# moistureMeasure.net
KiCad netlist of a schematic drawn in EAGLE
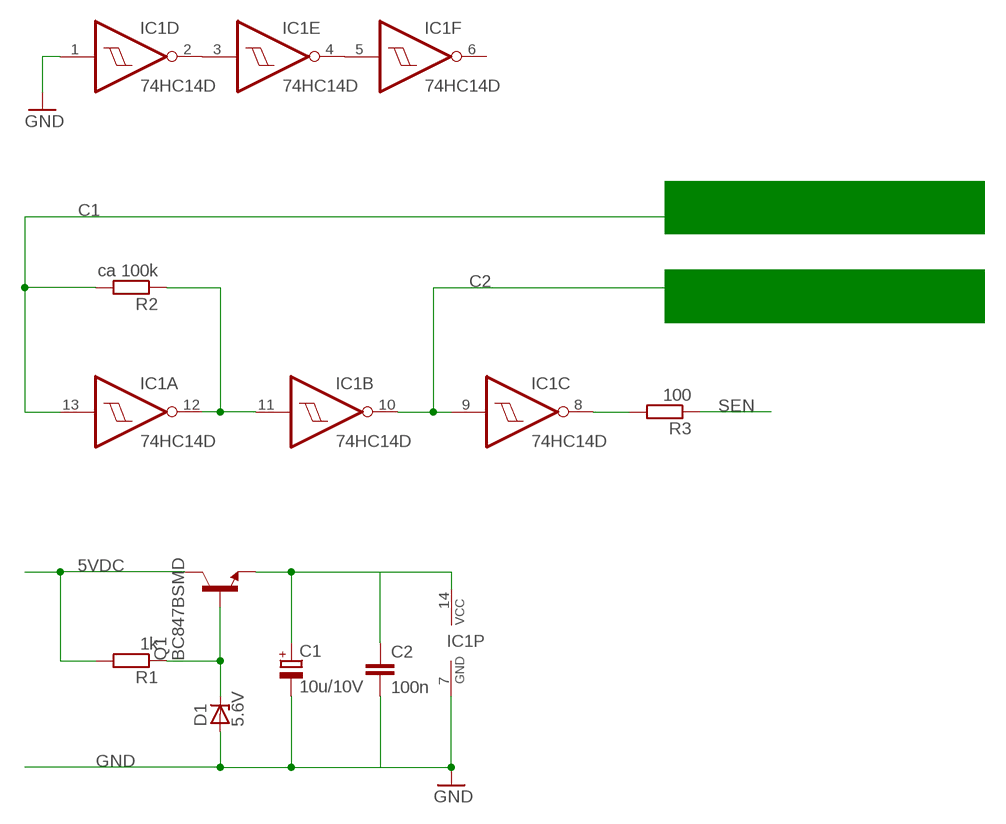
[diagram p0: schematic, sheet 1]

(export (version "E")
  (design (tool "Eeschema 10.0.6"))
  (components
    (comp (ref "C1")
      (value "10u/10V")
      (footprint "eagle-import:A_3216-18W")
      (libsource (lib "eagle-import") (part "CPOL-EUA/3216-18W"))
    )
    (comp (ref "C2")
      (value "100n")
      (footprint "eagle-import:C0805")
      (libsource (lib "eagle-import") (part "C-EUC0805"))
    )
    (comp (ref "D1")
      (value "5.6V")
      (footprint "eagle-import:SOD80C")
      (libsource (lib "eagle-import") (part "ZENER-DIODESOD80C"))
    )
    (comp (ref "IC1")
      (value "74HC14D")
      (footprint "eagle-import:SO14")
      (libsource (lib "eagle-import") (part "7414DHC"))
    )
    (comp (ref "Q1")
      (value "BC847BSMD")
      (footprint "eagle-import:SOT23")
      (libsource (lib "eagle-import") (part "BC847SMDB"))
    )
    (comp (ref "R1")
      (value "1k")
      (footprint "eagle-import:R0805")
      (libsource (lib "eagle-import") (part "R-EU_R0805"))
    )
    (comp (ref "R2")
      (value "ca 100k")
      (footprint "eagle-import:R0805")
      (libsource (lib "eagle-import") (part "R-EU_R0805"))
    )
    (comp (ref "R3")
      (value "100")
      (footprint "eagle-import:R0805")
      (libsource (lib "eagle-import") (part "R-EU_R0805"))
    )
  )
  (nets
    (net (code "1") (name "/5VDC") (class "Default")
      (node (ref "Q1") (pin "3") (pinfunction "C_3") (pintype "passive"))
      (node (ref "R1") (pin "2") (pinfunction "2_2") (pintype "passive"))
    )
    (net (code "2") (name "/C1") (class "Default")
      (node (ref "IC1") (pin "13") (pinfunction "I_13") (pintype "input"))
      (node (ref "R2") (pin "2") (pinfunction "2_2") (pintype "passive"))
    )
    (net (code "3") (name "/C2") (class "Default")
      (node (ref "IC1") (pin "10") (pinfunction "O_10") (pintype "output"))
      (node (ref "IC1") (pin "9") (pinfunction "I_9") (pintype "input"))
    )
    (net (code "4") (name "/SEN") (class "Default")
      (node (ref "R3") (pin "1") (pinfunction "1_1") (pintype "passive"))
    )
    (net (code "5") (name "GND") (class "Default")
      (node (ref "C1") (pin "-") (pinfunction "-_-") (pintype "passive"))
      (node (ref "C2") (pin "2") (pinfunction "2_2") (pintype "passive"))
      (node (ref "D1") (pin "A") (pinfunction "A_A") (pintype "passive"))
      (node (ref "IC1") (pin "1") (pinfunction "I_1") (pintype "input"))
      (node (ref "IC1") (pin "7") (pinfunction "GND_7") (pintype "power_in"))
    )
    (net (code "6") (name "Net-(IC1A-O)") (class "Default")
      (node (ref "IC1") (pin "11") (pinfunction "I_11") (pintype "input"))
      (node (ref "IC1") (pin "12") (pinfunction "O_12") (pintype "output"))
      (node (ref "R2") (pin "1") (pinfunction "1_1") (pintype "passive"))
    )
    (net (code "7") (name "Net-(IC1C-O)") (class "Default")
      (node (ref "IC1") (pin "8") (pinfunction "O_8") (pintype "output"))
      (node (ref "R3") (pin "2") (pinfunction "2_2") (pintype "passive"))
    )
    (net (code "8") (name "Net-(IC1D-O)") (class "Default")
      (node (ref "IC1") (pin "2") (pinfunction "O_2") (pintype "output"))
      (node (ref "IC1") (pin "3") (pinfunction "I_3") (pintype "input"))
    )
    (net (code "9") (name "Net-(IC1E-O)") (class "Default")
      (node (ref "IC1") (pin "4") (pinfunction "O_4") (pintype "output"))
      (node (ref "IC1") (pin "5") (pinfunction "I_5") (pintype "input"))
    )
    (net (code "10") (name "Net-(IC1G-VCC)") (class "Default")
      (node (ref "C1") (pin "+") (pinfunction "+_+") (pintype "passive"))
      (node (ref "C2") (pin "1") (pinfunction "1_1") (pintype "passive"))
      (node (ref "IC1") (pin "14") (pinfunction "VCC_14") (pintype "power_in"))
      (node (ref "Q1") (pin "2") (pinfunction "E_2") (pintype "passive"))
    )
    (net (code "11") (name "Net-(Q1-B)") (class "Default")
      (node (ref "D1") (pin "C") (pinfunction "C_C") (pintype "passive"))
      (node (ref "Q1") (pin "1") (pinfunction "B_1") (pintype "passive"))
      (node (ref "R1") (pin "1") (pinfunction "1_1") (pintype "passive"))
    )
    (net (code "12") (name "unconnected-(IC1F-O-Pad6)") (class "Default")
      (node (ref "IC1") (pin "6") (pinfunction "O_6") (pintype "output"))
    )
  )
)
